# v4_0.net
KiCad netlist of a schematic drawn in EAGLE
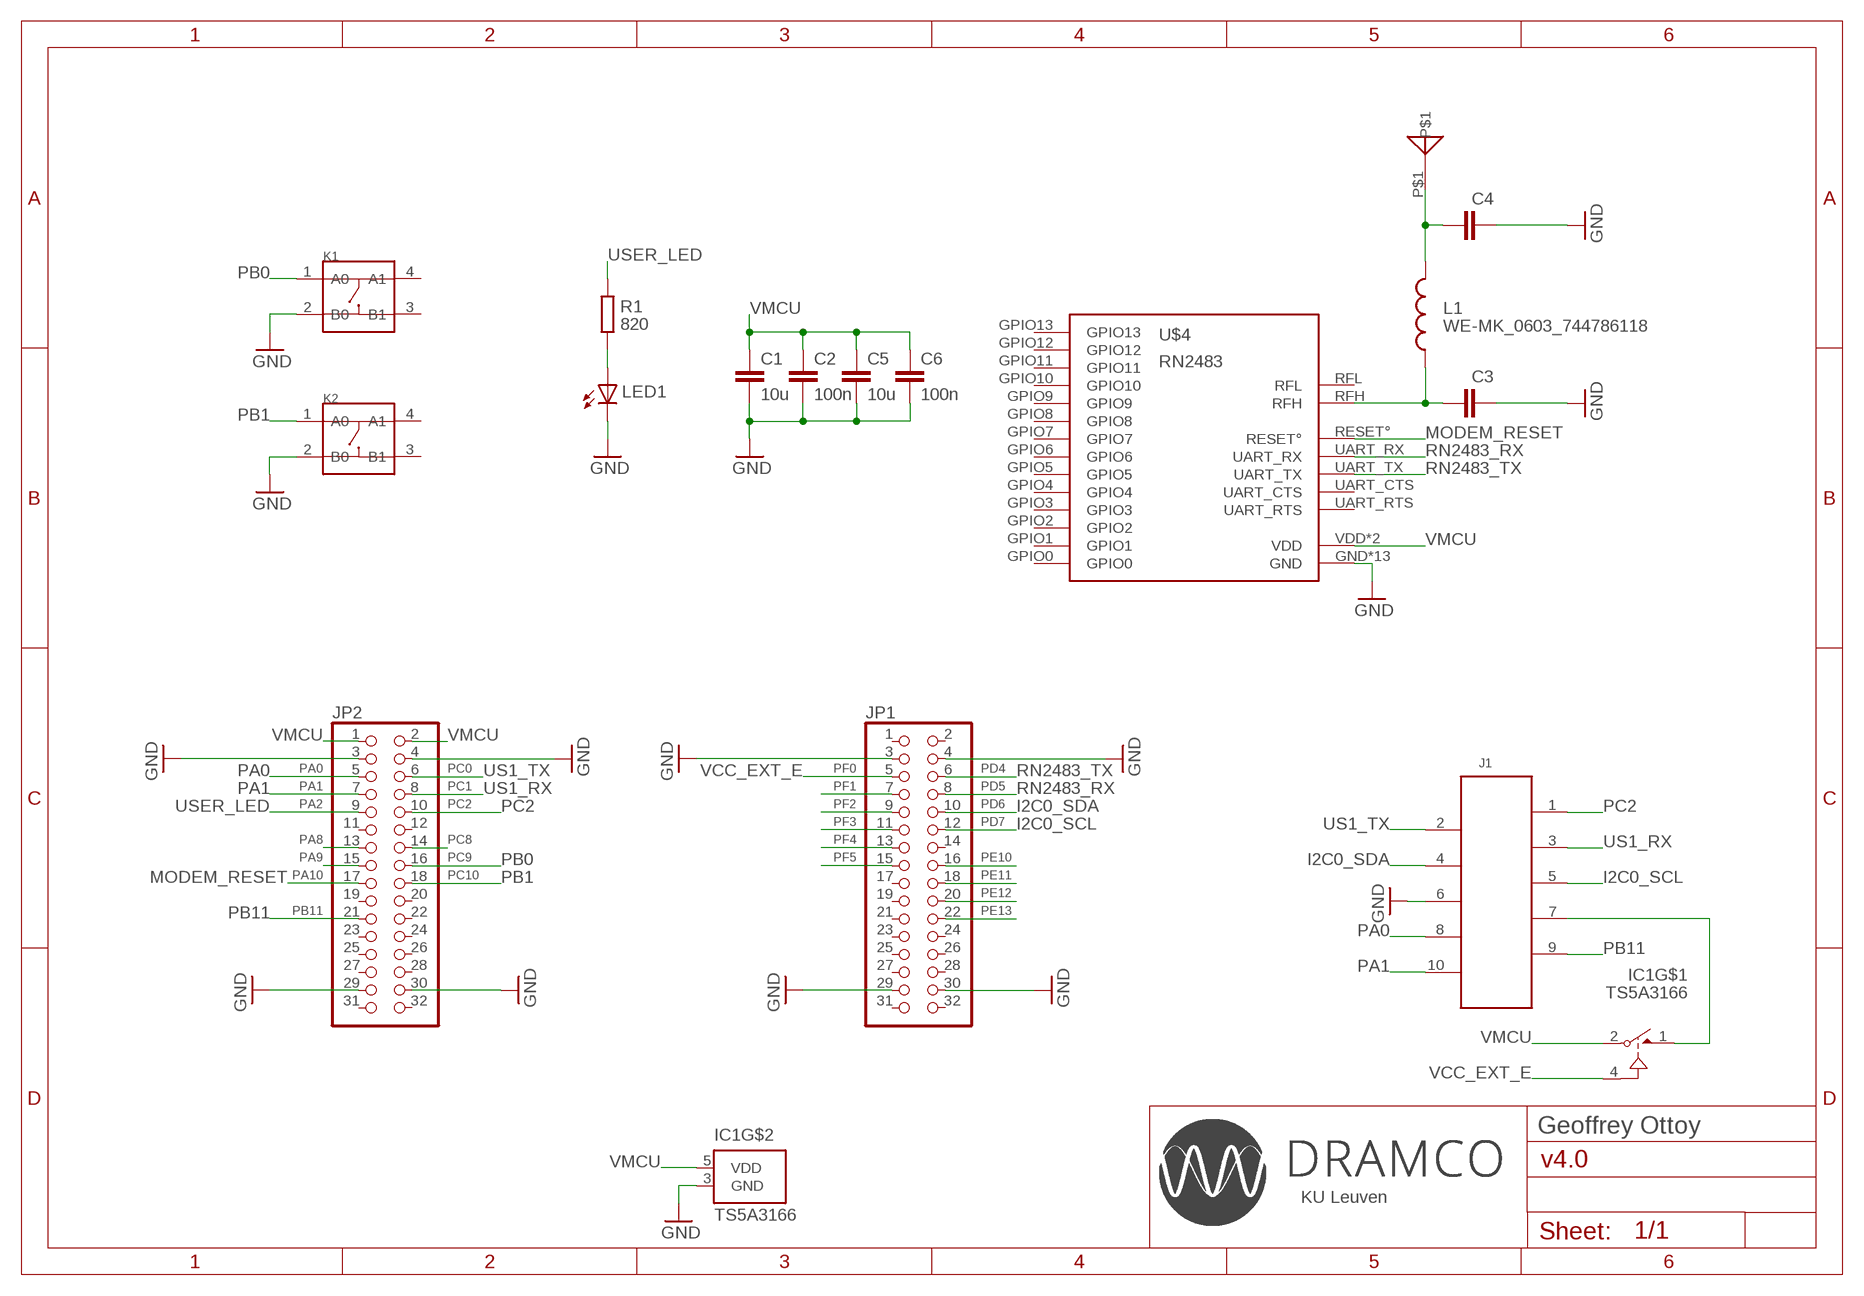
[diagram p0: schematic, sheet 1]

(export (version "E")
  (design (tool "Eeschema 10.0.6"))
  (components
    (comp (ref "C1")
      (value "10u")
      (footprint "eagle-import:C0805K")
      (libsource (lib "eagle-import") (part "C-EUC0805K"))
    )
    (comp (ref "C2")
      (value "100n")
      (footprint "eagle-import:C0805K")
      (libsource (lib "eagle-import") (part "C-EUC0805K"))
    )
    (comp (ref "C3")
      (value "C-EUC0603K")
      (footprint "eagle-import:C0603K")
      (libsource (lib "eagle-import") (part "C-EUC0603K"))
    )
    (comp (ref "C4")
      (value "C-EUC0603K")
      (footprint "eagle-import:C0603K")
      (libsource (lib "eagle-import") (part "C-EUC0603K"))
    )
    (comp (ref "C5")
      (value "10u")
      (footprint "eagle-import:C0805K")
      (libsource (lib "eagle-import") (part "C-EUC0805K"))
    )
    (comp (ref "C6")
      (value "100n")
      (footprint "eagle-import:C0805K")
      (libsource (lib "eagle-import") (part "C-EUC0805K"))
    )
    (comp (ref "IC1")
      (value "TS5A3166")
      (footprint "eagle-import:SC70-5L")
      (libsource (lib "eagle-import") (part "TS5A3166"))
    )
    (comp (ref "J1")
      (value "61001018321")
      (footprint "eagle-import:61001018321")
      (libsource (lib "eagle-import") (part "61001018321"))
    )
    (comp (ref "JP1")
      (value "PINHD-2X16")
      (footprint "eagle-import:2X16")
      (libsource (lib "eagle-import") (part "PINHD-2X16"))
    )
    (comp (ref "JP2")
      (value "PINHD-2X16")
      (footprint "eagle-import:2X16")
      (libsource (lib "eagle-import") (part "PINHD-2X16"))
    )
    (comp (ref "K1")
      (value "SMD-SWITCH-TACTILE-SPST-NO(4P-D6.0MM)")
      (footprint "eagle-import:SW4-SMD-6.0X6.0X5.0MM")
      (fields (field (name "MPN") "DTSM-62K-S-V-T/R(SN431)"))
      (libsource (lib "eagle-import") (part "SMD-SWITCH-TACTILE-SPST-NO(4P-D6.0MM)"))
    )
    (comp (ref "K2")
      (value "SMD-SWITCH-TACTILE-SPST-NO(4P-D6.0MM)")
      (footprint "eagle-import:SW4-SMD-6.0X6.0X5.0MM")
      (fields (field (name "MPN") "DTSM-62K-S-V-T/R(SN431)"))
      (libsource (lib "eagle-import") (part "SMD-SWITCH-TACTILE-SPST-NO(4P-D6.0MM)"))
    )
    (comp (ref "L1")
      (value "WE-MK_0603_744786118")
      (footprint "eagle-import:WE-MK_0603")
      (libsource (lib "eagle-import") (part "WE-MK_0603_744786118"))
    )
    (comp (ref "LED1")
      (value "LEDCHIPLED_0805")
      (footprint "eagle-import:CHIPLED_0805")
      (libsource (lib "eagle-import") (part "LEDCHIPLED_0805"))
    )
    (comp (ref "R1")
      (value "820")
      (footprint "eagle-import:R0805")
      (libsource (lib "eagle-import") (part "R-EU_R0805"))
    )
    (comp (ref "U$2")
      (value "ANTENNA868")
      (footprint "eagle-import:CERAMIC-ANTENNA")
      (libsource (lib "eagle-import") (part "ANTENNA868"))
    )
    (comp (ref "U$4")
      (value "RN2483")
      (footprint "eagle-import:RN2483")
      (libsource (lib "eagle-import") (part "RN2483"))
    )
  )
  (nets
    (net (code "1") (name "/PA0") (class "Default")
      (node (ref "J1") (pin "8") (pinfunction "3_8") (pintype "passive"))
      (node (ref "JP2") (pin "5") (pinfunction "5_5") (pintype "passive"))
    )
    (net (code "2") (name "/PA1") (class "Default")
      (node (ref "J1") (pin "10") (pinfunction "1_10") (pintype "passive"))
      (node (ref "JP2") (pin "7") (pinfunction "7_7") (pintype "passive"))
    )
    (net (code "3") (name "/PA2") (class "Default")
      (node (ref "JP2") (pin "9") (pinfunction "9_9") (pintype "passive"))
      (node (ref "R1") (pin "2") (pinfunction "2_2") (pintype "passive"))
    )
    (net (code "4") (name "/PA8") (class "Default")
      (node (ref "JP2") (pin "13") (pinfunction "13_13") (pintype "passive"))
    )
    (net (code "5") (name "/PA9") (class "Default")
      (node (ref "JP2") (pin "15") (pinfunction "15_15") (pintype "passive"))
    )
    (net (code "6") (name "/PA10") (class "Default")
      (node (ref "JP2") (pin "17") (pinfunction "17_17") (pintype "passive"))
      (node (ref "U$4") (pin "RESET°") (pinfunction "RESET°_RESET°") (pintype "bidirectional"))
    )
    (net (code "7") (name "/PB11") (class "Default")
      (node (ref "J1") (pin "9") (pinfunction "2_9") (pintype "passive"))
      (node (ref "JP2") (pin "21") (pinfunction "21_21") (pintype "passive"))
    )
    (net (code "8") (name "/PC0") (class "Default")
      (node (ref "J1") (pin "2") (pinfunction "9_2") (pintype "passive"))
      (node (ref "JP2") (pin "6") (pinfunction "6_6") (pintype "passive"))
    )
    (net (code "9") (name "/PC1") (class "Default")
      (node (ref "J1") (pin "3") (pinfunction "8_3") (pintype "passive"))
      (node (ref "JP2") (pin "8") (pinfunction "8_8") (pintype "passive"))
    )
    (net (code "10") (name "/PC2") (class "Default")
      (node (ref "J1") (pin "1") (pinfunction "10_1") (pintype "passive"))
      (node (ref "JP2") (pin "10") (pinfunction "10_10") (pintype "passive"))
    )
    (net (code "11") (name "/PC8") (class "Default")
      (node (ref "JP2") (pin "14") (pinfunction "14_14") (pintype "passive"))
    )
    (net (code "12") (name "/PC9") (class "Default")
      (node (ref "JP2") (pin "16") (pinfunction "16_16") (pintype "passive"))
      (node (ref "K1") (pin "1") (pinfunction "A0_1") (pintype "bidirectional"))
    )
    (net (code "13") (name "/PC10") (class "Default")
      (node (ref "JP2") (pin "18") (pinfunction "18_18") (pintype "passive"))
      (node (ref "K2") (pin "1") (pinfunction "A0_1") (pintype "bidirectional"))
    )
    (net (code "14") (name "/PD4") (class "Default")
      (node (ref "JP1") (pin "6") (pinfunction "6_6") (pintype "passive"))
      (node (ref "U$4") (pin "UART_TX") (pinfunction "UART_TX_UART_TX") (pintype "bidirectional"))
    )
    (net (code "15") (name "/PD5") (class "Default")
      (node (ref "JP1") (pin "8") (pinfunction "8_8") (pintype "passive"))
      (node (ref "U$4") (pin "UART_RX") (pinfunction "UART_RX_UART_RX") (pintype "bidirectional"))
    )
    (net (code "16") (name "/PD6") (class "Default")
      (node (ref "J1") (pin "4") (pinfunction "7_4") (pintype "passive"))
      (node (ref "JP1") (pin "10") (pinfunction "10_10") (pintype "passive"))
    )
    (net (code "17") (name "/PD7") (class "Default")
      (node (ref "J1") (pin "5") (pinfunction "6_5") (pintype "passive"))
      (node (ref "JP1") (pin "12") (pinfunction "12_12") (pintype "passive"))
    )
    (net (code "18") (name "/PE10") (class "Default")
      (node (ref "JP1") (pin "16") (pinfunction "16_16") (pintype "passive"))
    )
    (net (code "19") (name "/PE11") (class "Default")
      (node (ref "JP1") (pin "18") (pinfunction "18_18") (pintype "passive"))
    )
    (net (code "20") (name "/PE12") (class "Default")
      (node (ref "JP1") (pin "20") (pinfunction "20_20") (pintype "passive"))
    )
    (net (code "21") (name "/PE13") (class "Default")
      (node (ref "JP1") (pin "22") (pinfunction "22_22") (pintype "passive"))
    )
    (net (code "22") (name "/PF0") (class "Default")
      (node (ref "IC1") (pin "4") (pinfunction "IN_4") (pintype "input"))
      (node (ref "JP1") (pin "5") (pinfunction "5_5") (pintype "passive"))
    )
    (net (code "23") (name "/PF1") (class "Default")
      (node (ref "JP1") (pin "7") (pinfunction "7_7") (pintype "passive"))
    )
    (net (code "24") (name "/PF2") (class "Default")
      (node (ref "JP1") (pin "9") (pinfunction "9_9") (pintype "passive"))
    )
    (net (code "25") (name "/PF3") (class "Default")
      (node (ref "JP1") (pin "11") (pinfunction "11_11") (pintype "passive"))
    )
    (net (code "26") (name "/PF4") (class "Default")
      (node (ref "JP1") (pin "13") (pinfunction "13_13") (pintype "passive"))
    )
    (net (code "27") (name "/PF5") (class "Default")
      (node (ref "JP1") (pin "15") (pinfunction "15_15") (pintype "passive"))
    )
    (net (code "28") (name "/VMCU") (class "Default")
      (node (ref "C1") (pin "1") (pinfunction "1_1") (pintype "passive"))
      (node (ref "C2") (pin "1") (pinfunction "1_1") (pintype "passive"))
      (node (ref "C5") (pin "1") (pinfunction "1_1") (pintype "passive"))
      (node (ref "C6") (pin "1") (pinfunction "1_1") (pintype "passive"))
      (node (ref "IC1") (pin "2") (pinfunction "COM_2") (pintype "passive"))
      (node (ref "IC1") (pin "5") (pinfunction "VDD_5") (pintype "power_in"))
      (node (ref "JP2") (pin "1") (pinfunction "1_1") (pintype "passive"))
      (node (ref "JP2") (pin "2") (pinfunction "2_2") (pintype "passive"))
      (node (ref "U$4") (pin "VDD") (pinfunction "VDD_VDD") (pintype "bidirectional"))
      (node (ref "U$4") (pin "VDD2") (pinfunction "VDD_VDD2") (pintype "bidirectional"))
    )
    (net (code "29") (name "GND") (class "Default")
      (node (ref "C1") (pin "2") (pinfunction "2_2") (pintype "passive"))
      (node (ref "C2") (pin "2") (pinfunction "2_2") (pintype "passive"))
      (node (ref "C3") (pin "1") (pinfunction "1_1") (pintype "passive"))
      (node (ref "C4") (pin "1") (pinfunction "1_1") (pintype "passive"))
      (node (ref "C5") (pin "2") (pinfunction "2_2") (pintype "passive"))
      (node (ref "C6") (pin "2") (pinfunction "2_2") (pintype "passive"))
      (node (ref "IC1") (pin "3") (pinfunction "GND_3") (pintype "power_in"))
      (node (ref "J1") (pin "6") (pinfunction "5_6") (pintype "passive"))
      (node (ref "JP1") (pin "29") (pinfunction "29_29") (pintype "passive"))
      (node (ref "JP1") (pin "3") (pinfunction "3_3") (pintype "passive"))
      (node (ref "JP1") (pin "30") (pinfunction "30_30") (pintype "passive"))
      (node (ref "JP1") (pin "4") (pinfunction "4_4") (pintype "passive"))
      (node (ref "JP2") (pin "29") (pinfunction "29_29") (pintype "passive"))
      (node (ref "JP2") (pin "3") (pinfunction "3_3") (pintype "passive"))
      (node (ref "JP2") (pin "30") (pinfunction "30_30") (pintype "passive"))
      (node (ref "JP2") (pin "4") (pinfunction "4_4") (pintype "passive"))
      (node (ref "K1") (pin "2") (pinfunction "B0_2") (pintype "bidirectional"))
      (node (ref "K2") (pin "2") (pinfunction "B0_2") (pintype "bidirectional"))
      (node (ref "LED1") (pin "C") (pinfunction "C_C") (pintype "passive"))
      (node (ref "U$4") (pin "GND") (pinfunction "GND_GND") (pintype "bidirectional"))
      (node (ref "U$4") (pin "GND1") (pinfunction "GND_GND1") (pintype "bidirectional"))
      (node (ref "U$4") (pin "GND10") (pinfunction "GND_GND10") (pintype "bidirectional"))
      (node (ref "U$4") (pin "GND11") (pinfunction "GND_GND11") (pintype "bidirectional"))
      (node (ref "U$4") (pin "GND12") (pinfunction "GND_GND12") (pintype "bidirectional"))
      (node (ref "U$4") (pin "GND2") (pinfunction "GND_GND2") (pintype "bidirectional"))
      (node (ref "U$4") (pin "GND3") (pinfunction "GND_GND3") (pintype "bidirectional"))
      (node (ref "U$4") (pin "GND4") (pinfunction "GND_GND4") (pintype "bidirectional"))
      (node (ref "U$4") (pin "GND5") (pinfunction "GND_GND5") (pintype "bidirectional"))
      (node (ref "U$4") (pin "GND6") (pinfunction "GND_GND6") (pintype "bidirectional"))
      (node (ref "U$4") (pin "GND7") (pinfunction "GND_GND7") (pintype "bidirectional"))
      (node (ref "U$4") (pin "GND8") (pinfunction "GND_GND8") (pintype "bidirectional"))
      (node (ref "U$4") (pin "GND9") (pinfunction "GND_GND9") (pintype "bidirectional"))
    )
    (net (code "30") (name "Net-(C3-Pad2)") (class "Default")
      (node (ref "C3") (pin "2") (pinfunction "2_2") (pintype "passive"))
      (node (ref "L1") (pin "1") (pinfunction "1_1") (pintype "passive"))
      (node (ref "U$4") (pin "RFH") (pinfunction "RFH_RFH") (pintype "bidirectional"))
    )
    (net (code "31") (name "Net-(C4-Pad2)") (class "Default")
      (node (ref "C4") (pin "2") (pinfunction "2_2") (pintype "passive"))
      (node (ref "L1") (pin "2") (pinfunction "2_2") (pintype "passive"))
      (node (ref "U$2") (pin "P$1") (pinfunction "P$1_P$1") (pintype "bidirectional"))
    )
    (net (code "32") (name "Net-(IC1A-NO)") (class "Default")
      (node (ref "IC1") (pin "1") (pinfunction "NO_1") (pintype "passive"))
      (node (ref "J1") (pin "7") (pinfunction "4_7") (pintype "passive"))
    )
    (net (code "33") (name "Net-(LED1-PadA)") (class "Default")
      (node (ref "LED1") (pin "A") (pinfunction "A_A") (pintype "passive"))
      (node (ref "R1") (pin "1") (pinfunction "1_1") (pintype "passive"))
    )
    (net (code "34") (name "unconnected-(JP1-Pad1)") (class "Default")
      (node (ref "JP1") (pin "1") (pinfunction "1_1") (pintype "passive"))
    )
    (net (code "35") (name "unconnected-(JP1-Pad2)") (class "Default")
      (node (ref "JP1") (pin "2") (pinfunction "2_2") (pintype "passive"))
    )
    (net (code "36") (name "unconnected-(JP1-Pad14)") (class "Default")
      (node (ref "JP1") (pin "14") (pinfunction "14_14") (pintype "passive"))
    )
    (net (code "37") (name "unconnected-(JP1-Pad17)") (class "Default")
      (node (ref "JP1") (pin "17") (pinfunction "17_17") (pintype "passive"))
    )
    (net (code "38") (name "unconnected-(JP1-Pad19)") (class "Default")
      (node (ref "JP1") (pin "19") (pinfunction "19_19") (pintype "passive"))
    )
    (net (code "39") (name "unconnected-(JP1-Pad21)") (class "Default")
      (node (ref "JP1") (pin "21") (pinfunction "21_21") (pintype "passive"))
    )
    (net (code "40") (name "unconnected-(JP1-Pad23)") (class "Default")
      (node (ref "JP1") (pin "23") (pinfunction "23_23") (pintype "passive"))
    )
    (net (code "41") (name "unconnected-(JP1-Pad24)") (class "Default")
      (node (ref "JP1") (pin "24") (pinfunction "24_24") (pintype "passive"))
    )
    (net (code "42") (name "unconnected-(JP1-Pad25)") (class "Default")
      (node (ref "JP1") (pin "25") (pinfunction "25_25") (pintype "passive"))
    )
    (net (code "43") (name "unconnected-(JP1-Pad26)") (class "Default")
      (node (ref "JP1") (pin "26") (pinfunction "26_26") (pintype "passive"))
    )
    (net (code "44") (name "unconnected-(JP1-Pad27)") (class "Default")
      (node (ref "JP1") (pin "27") (pinfunction "27_27") (pintype "passive"))
    )
    (net (code "45") (name "unconnected-(JP1-Pad28)") (class "Default")
      (node (ref "JP1") (pin "28") (pinfunction "28_28") (pintype "passive"))
    )
    (net (code "46") (name "unconnected-(JP1-Pad31)") (class "Default")
      (node (ref "JP1") (pin "31") (pinfunction "31_31") (pintype "passive"))
    )
    (net (code "47") (name "unconnected-(JP1-Pad32)") (class "Default")
      (node (ref "JP1") (pin "32") (pinfunction "32_32") (pintype "passive"))
    )
    (net (code "48") (name "unconnected-(JP2-Pad11)") (class "Default")
      (node (ref "JP2") (pin "11") (pinfunction "11_11") (pintype "passive"))
    )
    (net (code "49") (name "unconnected-(JP2-Pad12)") (class "Default")
      (node (ref "JP2") (pin "12") (pinfunction "12_12") (pintype "passive"))
    )
    (net (code "50") (name "unconnected-(JP2-Pad19)") (class "Default")
      (node (ref "JP2") (pin "19") (pinfunction "19_19") (pintype "passive"))
    )
    (net (code "51") (name "unconnected-(JP2-Pad20)") (class "Default")
      (node (ref "JP2") (pin "20") (pinfunction "20_20") (pintype "passive"))
    )
    (net (code "52") (name "unconnected-(JP2-Pad22)") (class "Default")
      (node (ref "JP2") (pin "22") (pinfunction "22_22") (pintype "passive"))
    )
    (net (code "53") (name "unconnected-(JP2-Pad23)") (class "Default")
      (node (ref "JP2") (pin "23") (pinfunction "23_23") (pintype "passive"))
    )
    (net (code "54") (name "unconnected-(JP2-Pad24)") (class "Default")
      (node (ref "JP2") (pin "24") (pinfunction "24_24") (pintype "passive"))
    )
    (net (code "55") (name "unconnected-(JP2-Pad25)") (class "Default")
      (node (ref "JP2") (pin "25") (pinfunction "25_25") (pintype "passive"))
    )
    (net (code "56") (name "unconnected-(JP2-Pad26)") (class "Default")
      (node (ref "JP2") (pin "26") (pinfunction "26_26") (pintype "passive"))
    )
    (net (code "57") (name "unconnected-(JP2-Pad27)") (class "Default")
      (node (ref "JP2") (pin "27") (pinfunction "27_27") (pintype "passive"))
    )
    (net (code "58") (name "unconnected-(JP2-Pad28)") (class "Default")
      (node (ref "JP2") (pin "28") (pinfunction "28_28") (pintype "passive"))
    )
    (net (code "59") (name "unconnected-(JP2-Pad31)") (class "Default")
      (node (ref "JP2") (pin "31") (pinfunction "31_31") (pintype "passive"))
    )
    (net (code "60") (name "unconnected-(JP2-Pad32)") (class "Default")
      (node (ref "JP2") (pin "32") (pinfunction "32_32") (pintype "passive"))
    )
    (net (code "61") (name "unconnected-(K1-A1-Pad4)") (class "Default")
      (node (ref "K1") (pin "4") (pinfunction "A1_4") (pintype "bidirectional"))
    )
    (net (code "62") (name "unconnected-(K1-B1-Pad3)") (class "Default")
      (node (ref "K1") (pin "3") (pinfunction "B1_3") (pintype "bidirectional"))
    )
    (net (code "63") (name "unconnected-(K2-A1-Pad4)") (class "Default")
      (node (ref "K2") (pin "4") (pinfunction "A1_4") (pintype "bidirectional"))
    )
    (net (code "64") (name "unconnected-(K2-B1-Pad3)") (class "Default")
      (node (ref "K2") (pin "3") (pinfunction "B1_3") (pintype "bidirectional"))
    )
    (net (code "65") (name "unconnected-(U$4-PadGPIO0)") (class "Default")
      (node (ref "U$4") (pin "GPIO0") (pinfunction "GPIO0_GPIO0") (pintype "bidirectional"))
    )
    (net (code "66") (name "unconnected-(U$4-PadGPIO1)") (class "Default")
      (node (ref "U$4") (pin "GPIO1") (pinfunction "GPIO1_GPIO1") (pintype "bidirectional"))
    )
    (net (code "67") (name "unconnected-(U$4-PadGPIO2)") (class "Default")
      (node (ref "U$4") (pin "GPIO2") (pinfunction "GPIO2_GPIO2") (pintype "bidirectional"))
    )
    (net (code "68") (name "unconnected-(U$4-PadGPIO3)") (class "Default")
      (node (ref "U$4") (pin "GPIO3") (pinfunction "GPIO3_GPIO3") (pintype "bidirectional"))
    )
    (net (code "69") (name "unconnected-(U$4-PadGPIO4)") (class "Default")
      (node (ref "U$4") (pin "GPIO4") (pinfunction "GPIO4_GPIO4") (pintype "bidirectional"))
    )
    (net (code "70") (name "unconnected-(U$4-PadGPIO5)") (class "Default")
      (node (ref "U$4") (pin "GPIO5") (pinfunction "GPIO5_GPIO5") (pintype "bidirectional"))
    )
    (net (code "71") (name "unconnected-(U$4-PadGPIO6)") (class "Default")
      (node (ref "U$4") (pin "GPIO6") (pinfunction "GPIO6_GPIO6") (pintype "bidirectional"))
    )
    (net (code "72") (name "unconnected-(U$4-PadGPIO7)") (class "Default")
      (node (ref "U$4") (pin "GPIO7") (pinfunction "GPIO7_GPIO7") (pintype "bidirectional"))
    )
    (net (code "73") (name "unconnected-(U$4-PadGPIO8)") (class "Default")
      (node (ref "U$4") (pin "GPIO8") (pinfunction "GPIO8_GPIO8") (pintype "bidirectional"))
    )
    (net (code "74") (name "unconnected-(U$4-PadGPIO9)") (class "Default")
      (node (ref "U$4") (pin "GPIO9") (pinfunction "GPIO9_GPIO9") (pintype "bidirectional"))
    )
    (net (code "75") (name "unconnected-(U$4-PadGPIO10)") (class "Default")
      (node (ref "U$4") (pin "GPIO10") (pinfunction "GPIO10_GPIO10") (pintype "bidirectional"))
    )
    (net (code "76") (name "unconnected-(U$4-PadGPIO11)") (class "Default")
      (node (ref "U$4") (pin "GPIO11") (pinfunction "GPIO11_GPIO11") (pintype "bidirectional"))
    )
    (net (code "77") (name "unconnected-(U$4-PadGPIO12)") (class "Default")
      (node (ref "U$4") (pin "GPIO12") (pinfunction "GPIO12_GPIO12") (pintype "bidirectional"))
    )
    (net (code "78") (name "unconnected-(U$4-PadGPIO13)") (class "Default")
      (node (ref "U$4") (pin "GPIO13") (pinfunction "GPIO13_GPIO13") (pintype "bidirectional"))
    )
    (net (code "79") (name "unconnected-(U$4-PadRFL)") (class "Default")
      (node (ref "U$4") (pin "RFL") (pinfunction "RFL_RFL") (pintype "bidirectional"))
    )
    (net (code "80") (name "unconnected-(U$4-PadUART_CTS)") (class "Default")
      (node (ref "U$4") (pin "UART_CTS") (pinfunction "UART_CTS_UART_CTS") (pintype "bidirectional"))
    )
    (net (code "81") (name "unconnected-(U$4-PadUART_RTS)") (class "Default")
      (node (ref "U$4") (pin "UART_RTS") (pinfunction "UART_RTS_UART_RTS") (pintype "bidirectional"))
    )
  )
)
